# SensorsAndOthers.net
KiCad netlist of a schematic drawn in Altium Designer
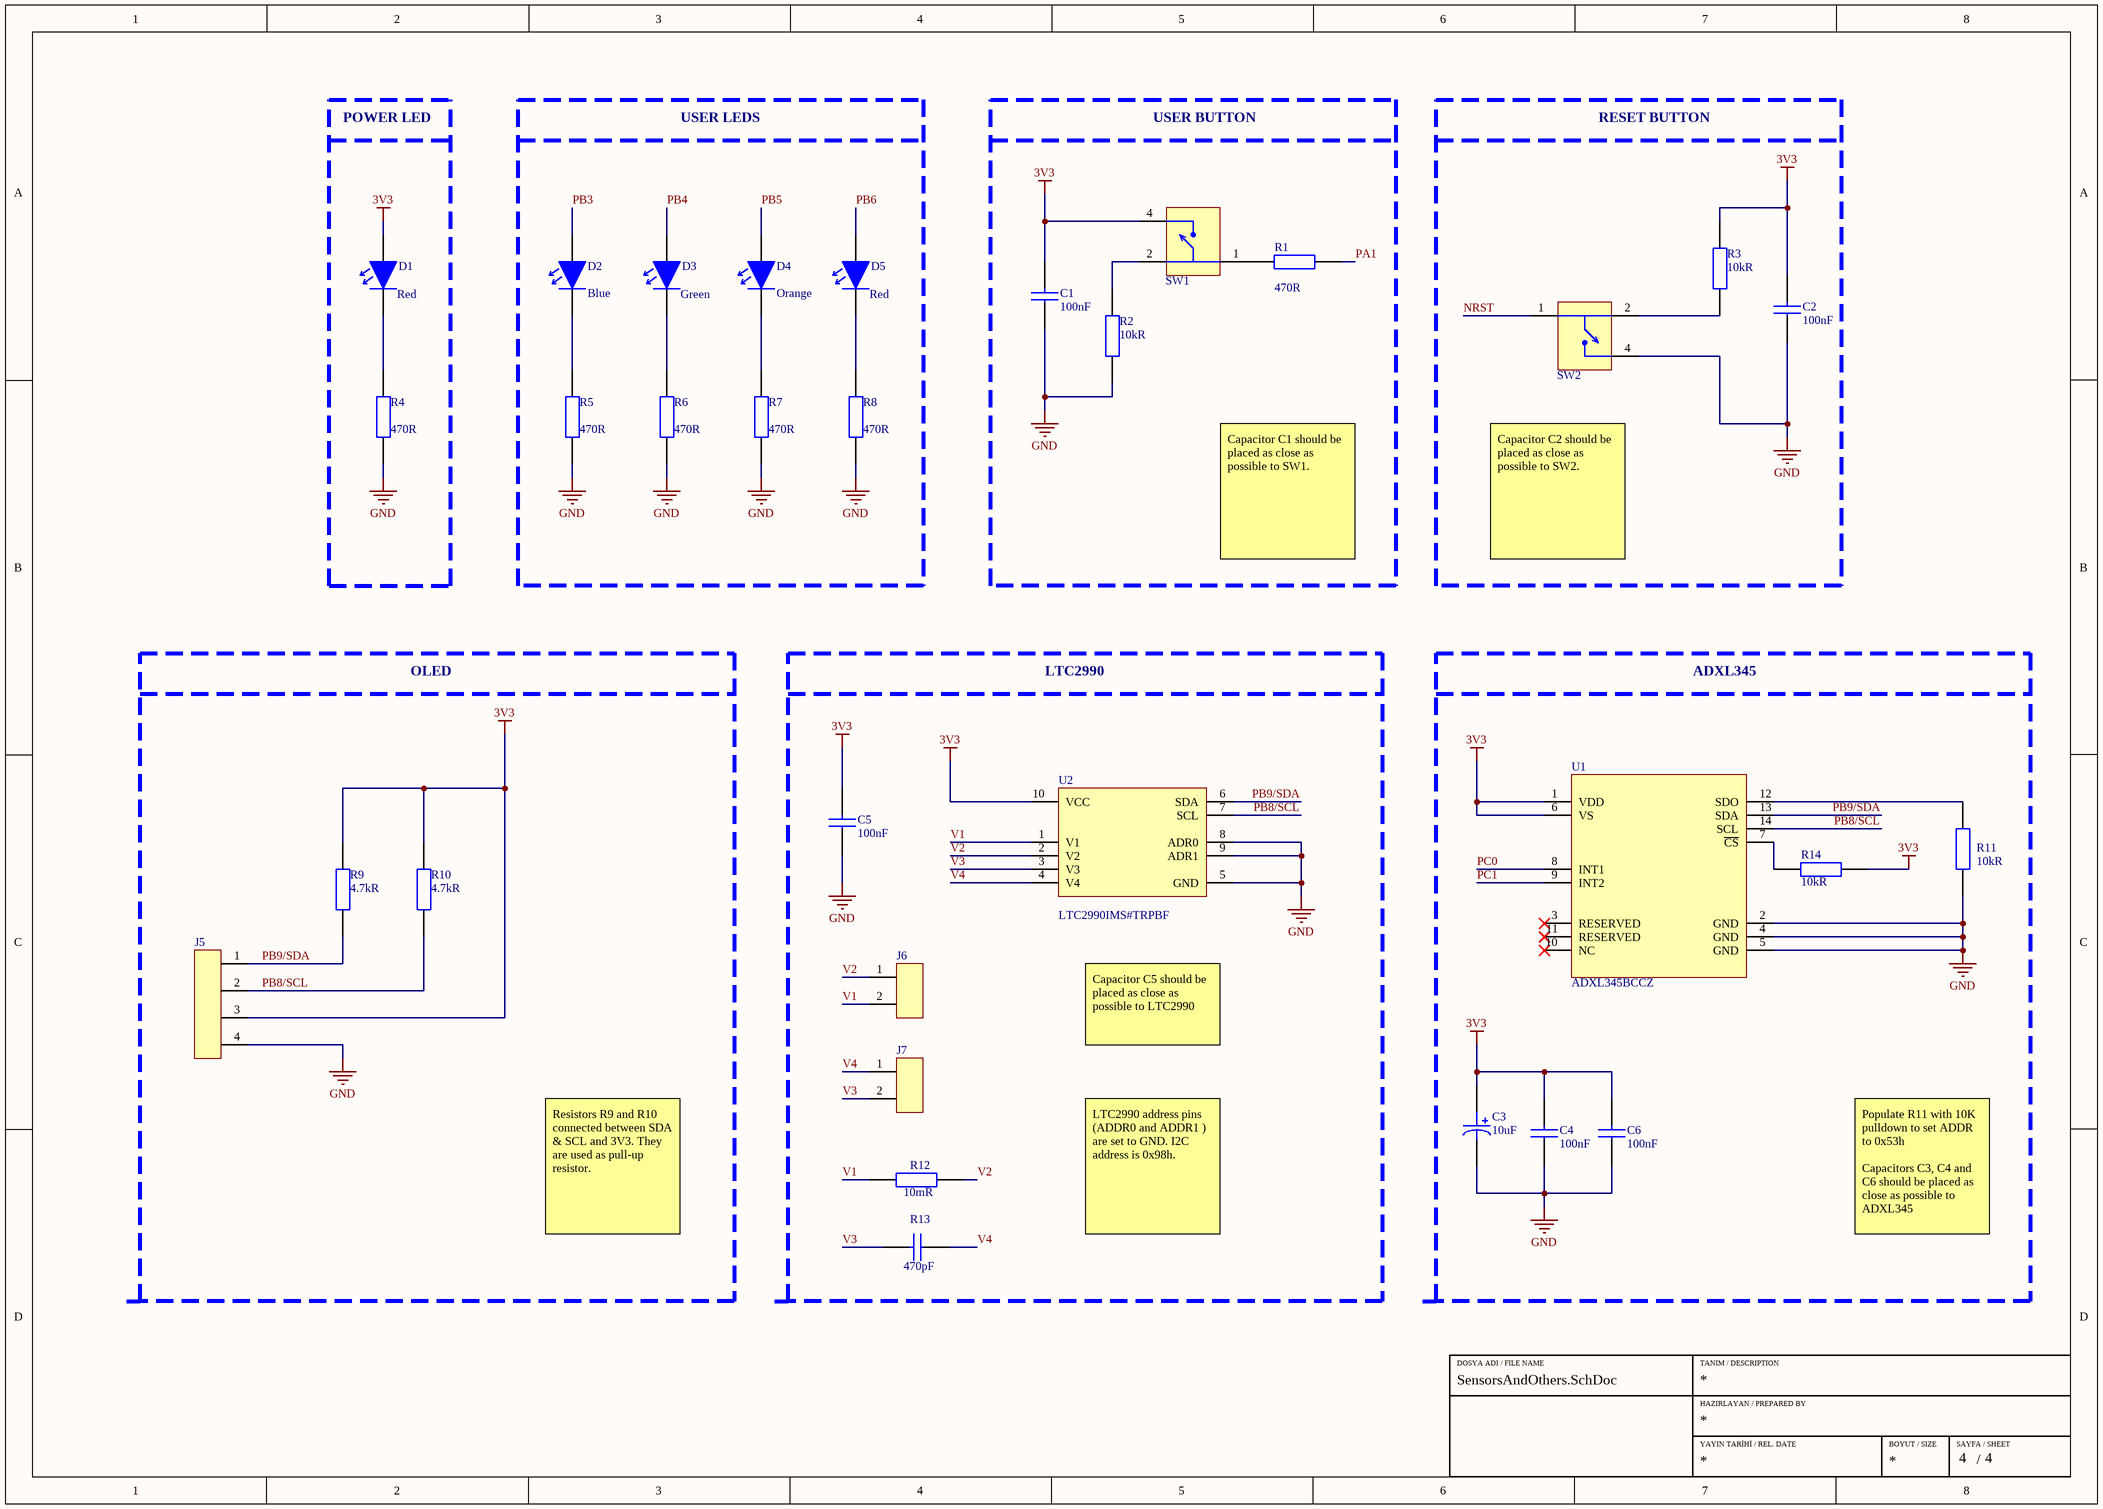
[diagram p0: SensorsAndOthers.SchDoc]

(export (version "E")
  (design (tool "Eeschema 10.0.6"))
  (components
    (comp (ref "C1")
      (value "CL21B104KBCNNNC")
      (footprint "CAP_0805")
      (description "CAP CER 100nF %10 0805")
      (fields
        (field (name "MANUFACTURER") "Samsung")
        (field (name "TOLERANCE") "10%")
        (field (name "CAPACITANCE") "100nF")
        (field (name "DESIGNED BY") "BERK")
      )
      (libsource (lib "Capacitors") (part "CAP CER 100nF 0805"))
    )
    (comp (ref "C2")
      (value "CL21B104KBCNNNC")
      (footprint "CAP_0805")
      (description "CAP CER 100nF %10 0805")
      (fields
        (field (name "MANUFACTURER") "Samsung")
        (field (name "TOLERANCE") "10%")
        (field (name "CAPACITANCE") "100nF")
        (field (name "DESIGNED BY") "BERK")
      )
      (libsource (lib "Capacitors") (part "CAP CER 100nF 0805"))
    )
    (comp (ref "C3")
      (value "T491A106K010AT")
      (footprint "CAP_1206_TANT")
      (description "Cap Tant Solid 10uF 10V A CASE 10% (3.2 X 1.6 X 1.6mm) SMD 3216-18 4 Ohm 125 C T/R")
      (fields
        (field (name "MANUFACTURER") "KEMET")
        (field (name "TOLERANCE") "10%")
        (field (name "CAPACITANCE") "10uF")
        (field (name "DESIGNED BY") "Aslı Kurt")
      )
      (libsource (lib "Capacitors") (part "CAP TANT 10uF 1206"))
    )
    (comp (ref "C4")
      (value "CL21B104KBCNNNC")
      (footprint "CAP_0805")
      (description "CAP CER 100nF %10 0805")
      (fields
        (field (name "MANUFACTURER") "Samsung")
        (field (name "TOLERANCE") "10%")
        (field (name "CAPACITANCE") "100nF")
        (field (name "DESIGNED BY") "BERK")
      )
      (libsource (lib "Capacitors") (part "CAP CER 100nF 0805"))
    )
    (comp (ref "C5")
      (value "CL21B104KBCNNNC")
      (footprint "CAP_0805")
      (description "CAP CER 100nF %10 0805")
      (fields
        (field (name "MANUFACTURER") "Samsung")
        (field (name "TOLERANCE") "10%")
        (field (name "CAPACITANCE") "100nF")
        (field (name "DESIGNED BY") "BERK")
      )
      (libsource (lib "Capacitors") (part "CAP CER 100nF 0805"))
    )
    (comp (ref "C6")
      (value "CL21B104KBCNNNC")
      (footprint "CAP_0805")
      (description "CAP CER 100nF %10 0805")
      (fields
        (field (name "MANUFACTURER") "Samsung")
        (field (name "TOLERANCE") "10%")
        (field (name "CAPACITANCE") "100nF")
        (field (name "DESIGNED BY") "BERK")
      )
      (libsource (lib "Capacitors") (part "CAP CER 100nF 0805"))
    )
    (comp (ref "D1")
      (value "LH R974-LP-1")
      (footprint "LED_RED_0805")
      (description "LED Uni-Color Hyper Red 660nm 2-Pin Chip 0805(2012Metric) T/R")
      (fields
        (field (name "MANUFACTURER") "Osram Opto")
        (field (name "COLOR") "Red")
        (field (name "DESIGNED BY") "BERK")
      )
      (libsource (lib "Diodes") (part "LED RED 0805"))
    )
    (comp (ref "D2")
      (value "150080BS75000")
      (footprint "LED_BLUE_0805")
      (description "LED BLUE CLEAR 0805 SMD")
      (fields
        (field (name "MANUFACTURER") "Wurth Electronics")
        (field (name "COLOR") "Blue")
        (field (name "DESIGNED BY") "Aslı Kurt")
      )
      (libsource (lib "Diodes") (part "LED BLUE 0805"))
    )
    (comp (ref "D3")
      (value "LTST-C171GKT")
      (footprint "LED_GREEN_0805")
      (description "Green 0805 130 º Min 5 mcd Typical 12 mcd Water Clear Lens SMT LED")
      (fields
        (field (name "MANUFACTURER") "Vishay Lite-On")
        (field (name "COLOR") "Green")
        (field (name "DESIGNED BY") "BERK")
      )
      (libsource (lib "Diodes") (part "LED GREEN 0805"))
    )
    (comp (ref "D4")
      (value "LTST-C170KFKT")
      (footprint "LED_ORANGE_0805")
      (description "LED Uni-Color Orange 611nm 2-Pin Chip LED T/R / LED ORANGE CLEAR 0805 SMD")
      (fields
        (field (name "MANUFACTURER") "Vishay Lite-On")
        (field (name "ILLUMINATION COLOR") "Orange")
        (field (name "DESIGNED BY") "Aslı Kurt")
      )
      (libsource (lib "Diodes") (part "LED ORANGE 0805"))
    )
    (comp (ref "D5")
      (value "LH R974-LP-1")
      (footprint "LED_RED_0805")
      (description "LED Uni-Color Hyper Red 660nm 2-Pin Chip 0805(2012Metric) T/R")
      (fields
        (field (name "MANUFACTURER") "Osram Opto")
        (field (name "COLOR") "Red")
        (field (name "DESIGNED BY") "BERK")
      )
      (libsource (lib "Diodes") (part "LED RED 0805"))
    )
    (comp (ref "J5")
      (value "PPTC041LFBN-RC")
      (footprint "4x1 Female Header 2.54mm")
      (description "CONN HEADER FEMALE 4POS .1 TIN")
      (fields (field (name "MANUFACTURER") "Sullins") (field (name "DESIGNED BY") "Aslı Kurt"))
      (libsource (lib "Connectors") (part "4x1 Female Header 2.54mm"))
    )
    (comp (ref "J6")
      (value "282836-2")
      (footprint "TERMINAL")
      (description "Connector, Terminal Block; Wire Receptacle; 2 Pos.; 16-30 AWG; 0.197 in. CL; Sid")
      (fields
        (field (name "MANUFACTURER") "TE Connectivity")
        (field (name "VOLTAGE") "300V")
        (field (name "DESIGNED BY") "Aslı Kurt")
      )
      (libsource (lib "Connectors") (part "2x1 TERMINAL 5mm"))
    )
    (comp (ref "J7")
      (value "282836-2")
      (footprint "TERMINAL")
      (description "Connector, Terminal Block; Wire Receptacle; 2 Pos.; 16-30 AWG; 0.197 in. CL; Sid")
      (fields
        (field (name "MANUFACTURER") "TE Connectivity")
        (field (name "VOLTAGE") "300V")
        (field (name "DESIGNED BY") "Aslı Kurt")
      )
      (libsource (lib "Connectors") (part "2x1 TERMINAL 5mm"))
    )
    (comp (ref "R1")
      (value "RC0805FR-07470RL")
      (footprint "RES_0805")
      (description "RES 470 OHM 1% 1/8W 0805")
      (fields
        (field (name "MANUFACTURER") "Yageo")
        (field (name "TOLERANCE") "1%")
        (field (name "RESISTANCE") "470R")
        (field (name "DESIGNED BY") "Aslı Kurt")
      )
      (libsource (lib "Resistors") (part "RES 470 OHM 0805"))
    )
    (comp (ref "R2")
      (value "RC0805JR-0710KL")
      (footprint "RES_0805")
      (description "RES 10K OHM 5% 1/8W 0805")
      (fields
        (field (name "MANUFACTURER") "Yageo")
        (field (name "TOLERANCE") "5%")
        (field (name "RESISTANCE") "10kR")
        (field (name "DESIGNED BY") "Aslı Kurt")
      )
      (libsource (lib "Resistors") (part "RES 10K OHM 0805"))
    )
    (comp (ref "R3")
      (value "RC0805JR-0710KL")
      (footprint "RES_0805")
      (description "RES 10K OHM 5% 1/8W 0805")
      (fields
        (field (name "MANUFACTURER") "Yageo")
        (field (name "TOLERANCE") "5%")
        (field (name "RESISTANCE") "10kR")
        (field (name "DESIGNED BY") "Aslı Kurt")
      )
      (libsource (lib "Resistors") (part "RES 10K OHM 0805"))
    )
    (comp (ref "R4")
      (value "RC0805FR-07470RL")
      (footprint "RES_0805")
      (description "RES 470 OHM 1% 1/8W 0805")
      (fields
        (field (name "MANUFACTURER") "Yageo")
        (field (name "TOLERANCE") "1%")
        (field (name "RESISTANCE") "470R")
        (field (name "DESIGNED BY") "Aslı Kurt")
      )
      (libsource (lib "") (part "RES 470 OHM 0805_1"))
    )
    (comp (ref "R5")
      (value "RC0805FR-07470RL")
      (footprint "RES_0805")
      (description "RES 470 OHM 1% 1/8W 0805")
      (fields
        (field (name "MANUFACTURER") "Yageo")
        (field (name "TOLERANCE") "1%")
        (field (name "RESISTANCE") "470R")
        (field (name "DESIGNED BY") "Aslı Kurt")
      )
      (libsource (lib "") (part "RES 470 OHM 0805_1"))
    )
    (comp (ref "R6")
      (value "RC0805FR-07470RL")
      (footprint "RES_0805")
      (description "RES 470 OHM 1% 1/8W 0805")
      (fields
        (field (name "MANUFACTURER") "Yageo")
        (field (name "TOLERANCE") "1%")
        (field (name "RESISTANCE") "470R")
        (field (name "DESIGNED BY") "Aslı Kurt")
      )
      (libsource (lib "") (part "RES 470 OHM 0805_1"))
    )
    (comp (ref "R7")
      (value "RC0805FR-07470RL")
      (footprint "RES_0805")
      (description "RES 470 OHM 1% 1/8W 0805")
      (fields
        (field (name "MANUFACTURER") "Yageo")
        (field (name "TOLERANCE") "1%")
        (field (name "RESISTANCE") "470R")
        (field (name "DESIGNED BY") "Aslı Kurt")
      )
      (libsource (lib "") (part "RES 470 OHM 0805_1"))
    )
    (comp (ref "R8")
      (value "RC0805FR-07470RL")
      (footprint "RES_0805")
      (description "RES 470 OHM 1% 1/8W 0805")
      (fields
        (field (name "MANUFACTURER") "Yageo")
        (field (name "TOLERANCE") "1%")
        (field (name "RESISTANCE") "470R")
        (field (name "DESIGNED BY") "Aslı Kurt")
      )
      (libsource (lib "") (part "RES 470 OHM 0805_1"))
    )
    (comp (ref "R9")
      (value "RC0603JR-074K7L")
      (footprint "RES_0603")
      (description "RES 4K7 %5 OHM 0603 SMD")
      (fields
        (field (name "MANUFACTURER") "Yageo")
        (field (name "TOLERANCE") "5%")
        (field (name "RESISTANCE") "4.7kR")
        (field (name "DESIGNED BY") "Aslı Kurt")
      )
      (libsource (lib "Resistors") (part "RES 4K7 OHM 0603"))
    )
    (comp (ref "R10")
      (value "RC0603JR-074K7L")
      (footprint "RES_0603")
      (description "RES 4K7 %5 OHM 0603 SMD")
      (fields
        (field (name "MANUFACTURER") "Yageo")
        (field (name "TOLERANCE") "5%")
        (field (name "RESISTANCE") "4.7kR")
        (field (name "DESIGNED BY") "Aslı Kurt")
      )
      (libsource (lib "Resistors") (part "RES 4K7 OHM 0603"))
    )
    (comp (ref "R11")
      (value "RC0805JR-0710KL")
      (footprint "RES_0805")
      (description "RES 10K OHM 5% 1/8W 0805")
      (fields
        (field (name "MANUFACTURER") "Yageo")
        (field (name "TOLERANCE") "5%")
        (field (name "RESISTANCE") "10kR")
        (field (name "DESIGNED BY") "Aslı Kurt")
      )
      (libsource (lib "Resistors") (part "RES 10K OHM 0805"))
    )
    (comp (ref "R12")
      (value "RL1206FR-070R01L")
      (footprint "RES_1206")
      (description "Res Thick Film 1206 0.01 Ohm 1% 0.25W(1/4W) ±1500ppm/C Pad SMD Automotive T/R")
      (fields
        (field (name "MANUFACTURER") "Yageo")
        (field (name "RESISTANCE") "10mR")
        (field (name "DESIGNED BY") "Aslı Kurt")
      )
      (libsource (lib "Resistors") (part "RES 10m OHM 1206"))
    )
    (comp (ref "R13")
      (value "CC0805KRX7R9BB471")
      (footprint "CAP_0805")
      (description "CAP CER 470PF 50V X7R 0805")
      (fields
        (field (name "MANUFACTURER") "Yageo")
        (field (name "CAPACITANCE") "470pF")
        (field (name "DESIGNED BY") "Aslı Kurt")
      )
      (libsource (lib "Capacitors") (part "CAP CER 470pF 0805"))
    )
    (comp (ref "R14")
      (value "RC0603FR-0710KL")
      (footprint "RES_0603")
      (description "RES 10K %1 OHM 0603 SMD")
      (fields
        (field (name "MANUFACTURER") "Yageo")
        (field (name "TOLERANCE") "1%")
        (field (name "RESISTANCE") "10kR")
        (field (name "DESIGNEDBY") "Aslı Kurt")
      )
      (libsource (lib "MyLibrary") (part "RES 10K OHM 0603"))
    )
    (comp (ref "SW1")
      (value "PTS815 SJK 250 SMTR LFS")
      (footprint "BUTTON SMD")
      (description "Microminiature Top Actuated Tactile Switch Momentary SPST-NO 50mA 12VDC Surface Mount T/R")
      (fields
        (field (name "MANUFACTURER") "ITT C&K")
        (field (name "MANUFACTURER PART NUMBER") "PTS815SJK250SMTRLFS")
        (field (name "DESIGNED BY") "Aslı Kurt")
      )
      (libsource (lib "Connectors") (part "4.2mm x 3.2mm BUTTON"))
    )
    (comp (ref "SW2")
      (value "PTS815 SJK 250 SMTR LFS")
      (footprint "BUTTON SMD")
      (description "Microminiature Top Actuated Tactile Switch Momentary SPST-NO 50mA 12VDC Surface Mount T/R")
      (fields
        (field (name "MANUFACTURER") "ITT C&K")
        (field (name "MANUFACTURER PART NUMBER") "PTS815SJK250SMTRLFS")
        (field (name "DESIGNED BY") "Aslı Kurt")
      )
      (libsource (lib "") (part "4.2mm x 3.2mm BUTTON_1"))
    )
    (comp (ref "U1")
      (value "ADXL345BCCZ")
      (footprint "14-VFLGA")
      (fields (field (name "MANUFACTURER") "Analog Devices") (field (name "DESIGNED BY") "Aslı Kurt"))
      (libsource (lib "SensorsAndOthers") (part "ADXL345BCCZ"))
    )
    (comp (ref "U2")
      (value "LTC2990IMS#TRPBF")
      (footprint "MSOP-10")
      (description "Ms-System Monitor/Other I2c Temperature, Voltage And Current Monitor")
      (fields
        (field (name "MANUFACTURER") "Analog Devices / Linear Technology")
        (field (name "DESIGNED BY") "Aslı Kurt")
      )
      (libsource (lib "SensorsAndOthers") (part "LTC2990IMS#TRPBF"))
    )
  )
  (nets
    (net (code "1") (name "/NRST") (class "Default")
      (node (ref "SW2") (pin "1") (pinfunction "1_1") (pintype "passive"))
    )
    (net (code "2") (name "/PA1") (class "Default")
      (node (ref "R1") (pin "2") (pinfunction "2_2") (pintype "passive"))
    )
    (net (code "3") (name "/PB3") (class "Default")
      (node (ref "D2") (pin "2") (pinfunction "2_2") (pintype "power_in"))
    )
    (net (code "4") (name "/PB4") (class "Default")
      (node (ref "D3") (pin "2") (pinfunction "2_2") (pintype "power_in"))
    )
    (net (code "5") (name "/PB5") (class "Default")
      (node (ref "D4") (pin "2") (pinfunction "2_2") (pintype "power_in"))
    )
    (net (code "6") (name "/PB6") (class "Default")
      (node (ref "D5") (pin "2") (pinfunction "2_2") (pintype "power_in"))
    )
    (net (code "7") (name "/PB8{slash}SCL") (class "Default")
      (node (ref "J5") (pin "2") (pinfunction "2_2") (pintype "power_in"))
      (node (ref "R10") (pin "1") (pinfunction "1_1") (pintype "passive"))
      (node (ref "U1") (pin "14") (pinfunction "SCL_14") (pintype "passive"))
      (node (ref "U2") (pin "7") (pinfunction "SCL_7") (pintype "passive"))
    )
    (net (code "8") (name "/PB9{slash}SDA") (class "Default")
      (node (ref "J5") (pin "1") (pinfunction "1_1") (pintype "power_in"))
      (node (ref "R9") (pin "1") (pinfunction "1_1") (pintype "passive"))
      (node (ref "U1") (pin "13") (pinfunction "SDA_13") (pintype "passive"))
      (node (ref "U2") (pin "6") (pinfunction "SDA_6") (pintype "passive"))
    )
    (net (code "9") (name "/PC0") (class "Default")
      (node (ref "U1") (pin "8") (pinfunction "INT1_8") (pintype "passive"))
    )
    (net (code "10") (name "/PC1") (class "Default")
      (node (ref "U1") (pin "9") (pinfunction "INT2_9") (pintype "passive"))
    )
    (net (code "11") (name "/V1") (class "Default")
      (node (ref "J6") (pin "2") (pinfunction "2_2") (pintype "passive"))
      (node (ref "R12") (pin "2") (pinfunction "2_2") (pintype "passive"))
      (node (ref "U2") (pin "1") (pinfunction "V1_1") (pintype "passive"))
    )
    (net (code "12") (name "/V2") (class "Default")
      (node (ref "J6") (pin "1") (pinfunction "1_1") (pintype "passive"))
      (node (ref "R12") (pin "1") (pinfunction "1_1") (pintype "passive"))
      (node (ref "U2") (pin "2") (pinfunction "V2_2") (pintype "passive"))
    )
    (net (code "13") (name "/V3") (class "Default")
      (node (ref "J7") (pin "2") (pinfunction "2_2") (pintype "passive"))
      (node (ref "R13") (pin "2") (pinfunction "2_2") (pintype "passive"))
      (node (ref "U2") (pin "3") (pinfunction "V3_3") (pintype "passive"))
    )
    (net (code "14") (name "/V4") (class "Default")
      (node (ref "J7") (pin "1") (pinfunction "1_1") (pintype "passive"))
      (node (ref "R13") (pin "1") (pinfunction "1_1") (pintype "passive"))
      (node (ref "U2") (pin "4") (pinfunction "V4_4") (pintype "passive"))
    )
    (net (code "15") (name "3V3") (class "Default")
      (node (ref "C1") (pin "2") (pinfunction "2_2") (pintype "passive"))
      (node (ref "C2") (pin "2") (pinfunction "2_2") (pintype "passive"))
      (node (ref "C3") (pin "1") (pinfunction "1_1") (pintype "passive"))
      (node (ref "C4") (pin "2") (pinfunction "2_2") (pintype "passive"))
      (node (ref "C5") (pin "2") (pinfunction "2_2") (pintype "passive"))
      (node (ref "C6") (pin "2") (pinfunction "2_2") (pintype "passive"))
      (node (ref "D1") (pin "2") (pinfunction "2_2") (pintype "power_in"))
      (node (ref "J5") (pin "3") (pinfunction "3_3") (pintype "power_in"))
      (node (ref "R10") (pin "2") (pinfunction "2_2") (pintype "passive"))
      (node (ref "R14") (pin "2") (pinfunction "2_2") (pintype "passive"))
      (node (ref "R3") (pin "2") (pinfunction "2_2") (pintype "passive"))
      (node (ref "R9") (pin "2") (pinfunction "2_2") (pintype "passive"))
      (node (ref "SW1") (pin "4") (pinfunction "4_4") (pintype "passive"))
      (node (ref "U1") (pin "1") (pinfunction "VDD_1") (pintype "passive"))
      (node (ref "U1") (pin "6") (pinfunction "VS_6") (pintype "passive"))
      (node (ref "U2") (pin "10") (pinfunction "VCC_10") (pintype "passive"))
    )
    (net (code "16") (name "GND") (class "Default")
      (node (ref "C1") (pin "1") (pinfunction "1_1") (pintype "passive"))
      (node (ref "C2") (pin "1") (pinfunction "1_1") (pintype "passive"))
      (node (ref "C3") (pin "2") (pinfunction "2_2") (pintype "passive"))
      (node (ref "C4") (pin "1") (pinfunction "1_1") (pintype "passive"))
      (node (ref "C5") (pin "1") (pinfunction "1_1") (pintype "passive"))
      (node (ref "C6") (pin "1") (pinfunction "1_1") (pintype "passive"))
      (node (ref "J5") (pin "4") (pinfunction "4_4") (pintype "power_in"))
      (node (ref "R11") (pin "1") (pinfunction "1_1") (pintype "passive"))
      (node (ref "R2") (pin "1") (pinfunction "1_1") (pintype "passive"))
      (node (ref "R4") (pin "1") (pinfunction "1_1") (pintype "passive"))
      (node (ref "R5") (pin "1") (pinfunction "1_1") (pintype "passive"))
      (node (ref "R6") (pin "1") (pinfunction "1_1") (pintype "passive"))
      (node (ref "R7") (pin "1") (pinfunction "1_1") (pintype "passive"))
      (node (ref "R8") (pin "1") (pinfunction "1_1") (pintype "passive"))
      (node (ref "SW2") (pin "4") (pinfunction "4_4") (pintype "passive"))
      (node (ref "U1") (pin "2") (pinfunction "GND_2") (pintype "passive"))
      (node (ref "U1") (pin "4") (pinfunction "GND_4") (pintype "passive"))
      (node (ref "U1") (pin "5") (pinfunction "GND_5") (pintype "passive"))
      (node (ref "U2") (pin "5") (pinfunction "GND_5") (pintype "passive"))
      (node (ref "U2") (pin "8") (pinfunction "ADR0_8") (pintype "passive"))
      (node (ref "U2") (pin "9") (pinfunction "ADR1_9") (pintype "passive"))
    )
    (net (code "17") (name "Net-(D1-Pad1)") (class "Default")
      (node (ref "D1") (pin "1") (pinfunction "1_1") (pintype "power_in"))
      (node (ref "R4") (pin "2") (pinfunction "2_2") (pintype "passive"))
    )
    (net (code "18") (name "Net-(D2-Pad1)") (class "Default")
      (node (ref "D2") (pin "1") (pinfunction "1_1") (pintype "power_in"))
      (node (ref "R5") (pin "2") (pinfunction "2_2") (pintype "passive"))
    )
    (net (code "19") (name "Net-(D3-Pad1)") (class "Default")
      (node (ref "D3") (pin "1") (pinfunction "1_1") (pintype "power_in"))
      (node (ref "R6") (pin "2") (pinfunction "2_2") (pintype "passive"))
    )
    (net (code "20") (name "Net-(D4-Pad1)") (class "Default")
      (node (ref "D4") (pin "1") (pinfunction "1_1") (pintype "power_in"))
      (node (ref "R7") (pin "2") (pinfunction "2_2") (pintype "passive"))
    )
    (net (code "21") (name "Net-(D5-Pad1)") (class "Default")
      (node (ref "D5") (pin "1") (pinfunction "1_1") (pintype "power_in"))
      (node (ref "R8") (pin "2") (pinfunction "2_2") (pintype "passive"))
    )
    (net (code "22") (name "Net-(R1-Pad1)") (class "Default")
      (node (ref "R1") (pin "1") (pinfunction "1_1") (pintype "passive"))
      (node (ref "SW1") (pin "1") (pinfunction "1_1") (pintype "passive"))
    )
    (net (code "23") (name "Net-(R2-Pad2)") (class "Default")
      (node (ref "R2") (pin "2") (pinfunction "2_2") (pintype "passive"))
      (node (ref "SW1") (pin "2") (pinfunction "2_2") (pintype "passive"))
    )
    (net (code "24") (name "Net-(R3-Pad1)") (class "Default")
      (node (ref "R3") (pin "1") (pinfunction "1_1") (pintype "passive"))
      (node (ref "SW2") (pin "2") (pinfunction "2_2") (pintype "passive"))
    )
    (net (code "25") (name "Net-(U1-SDO)") (class "Default")
      (node (ref "R11") (pin "2") (pinfunction "2_2") (pintype "passive"))
      (node (ref "U1") (pin "12") (pinfunction "SDO_12") (pintype "passive"))
    )
    (net (code "26") (name "Net-(U1-~{CS})") (class "Default")
      (node (ref "R14") (pin "1") (pinfunction "1_1") (pintype "passive"))
      (node (ref "U1") (pin "7") (pinfunction "~{CS}_7") (pintype "passive"))
    )
    (net (code "27") (name "unconnected-(U1-NC-Pad10)") (class "Default")
      (node (ref "U1") (pin "10") (pinfunction "NC_10") (pintype "passive+no_connect"))
    )
    (net (code "28") (name "unconnected-(U1-RESERVED-Pad3)") (class "Default")
      (node (ref "U1") (pin "3") (pinfunction "RESERVED_3") (pintype "passive+no_connect"))
    )
    (net (code "29") (name "unconnected-(U1-RESERVED-Pad11)") (class "Default")
      (node (ref "U1") (pin "11") (pinfunction "RESERVED_11") (pintype "passive+no_connect"))
    )
  )
)
